# radencoder_rechts.net
KiCad netlist of a schematic drawn in EAGLE
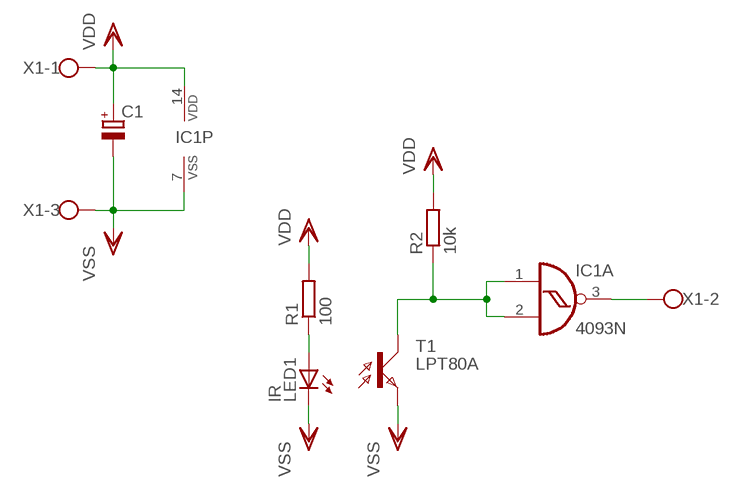
[diagram p0: schematic, sheet 1]

(export (version "E")
  (design (tool "Eeschema 10.0.6"))
  (components
    (comp (ref "C1")
      (value "CPOL-EUE5-10.5")
      (footprint "eagle-import:E5-10,5")
      (libsource (lib "eagle-import") (part "CPOL-EUE5-10.5"))
    )
    (comp (ref "IC1")
      (value "4093N")
      (footprint "eagle-import:DIL14")
      (libsource (lib "eagle-import") (part "4093N"))
    )
    (comp (ref "LED1")
      (value "IR")
      (footprint "eagle-import:LED5MM")
      (libsource (lib "eagle-import") (part "LED5MM"))
    )
    (comp (ref "R1")
      (value "100")
      (footprint "eagle-import:0207_10")
      (libsource (lib "eagle-import") (part "R-EU_0207/10"))
    )
    (comp (ref "R2")
      (value "10k")
      (footprint "eagle-import:0207_10")
      (libsource (lib "eagle-import") (part "R-EU_0207/10"))
    )
    (comp (ref "T1")
      (value "LPT80A")
      (footprint "eagle-import:LPT80A")
      (libsource (lib "eagle-import") (part "LPT80A"))
    )
    (comp (ref "X1")
      (value "W237-103")
      (footprint "eagle-import:W237-103")
      (fields (field (name "MPN") "237-103"))
      (libsource (lib "eagle-import") (part "W237-103"))
    )
  )
  (nets
    (net (code "1") (name "Net-(IC1A-I0)") (class "Default")
      (node (ref "IC1") (pin "1") (pinfunction "I0_1") (pintype "input"))
      (node (ref "IC1") (pin "2") (pinfunction "I1_2") (pintype "input"))
      (node (ref "R2") (pin "1") (pinfunction "1_1") (pintype "passive"))
      (node (ref "T1") (pin "C") (pinfunction "C_C") (pintype "passive"))
    )
    (net (code "2") (name "Net-(IC1A-O)") (class "Default")
      (node (ref "IC1") (pin "3") (pinfunction "O_3") (pintype "output"))
      (node (ref "X1") (pin "2") (pinfunction "KL_2") (pintype "passive"))
    )
    (net (code "3") (name "Net-(LED1-PadA)") (class "Default")
      (node (ref "LED1") (pin "A") (pinfunction "A_A") (pintype "passive"))
      (node (ref "R1") (pin "1") (pinfunction "1_1") (pintype "passive"))
    )
    (net (code "4") (name "VDD") (class "Default")
      (node (ref "C1") (pin "+") (pinfunction "+_+") (pintype "passive"))
      (node (ref "IC1") (pin "14") (pinfunction "VDD_14") (pintype "power_in"))
      (node (ref "R1") (pin "2") (pinfunction "2_2") (pintype "passive"))
      (node (ref "R2") (pin "2") (pinfunction "2_2") (pintype "passive"))
      (node (ref "X1") (pin "1") (pinfunction "KL_1") (pintype "passive"))
    )
    (net (code "5") (name "VSS") (class "Default")
      (node (ref "C1") (pin "-") (pinfunction "-_-") (pintype "passive"))
      (node (ref "IC1") (pin "7") (pinfunction "VSS_7") (pintype "power_in"))
      (node (ref "LED1") (pin "K") (pinfunction "C_K") (pintype "passive"))
      (node (ref "T1") (pin "E") (pinfunction "E_E") (pintype "passive"))
      (node (ref "X1") (pin "3") (pinfunction "KL_3") (pintype "passive"))
    )
  )
)
